# Adapter-IO4-Grove.net
KiCad netlist of a schematic drawn in EAGLE
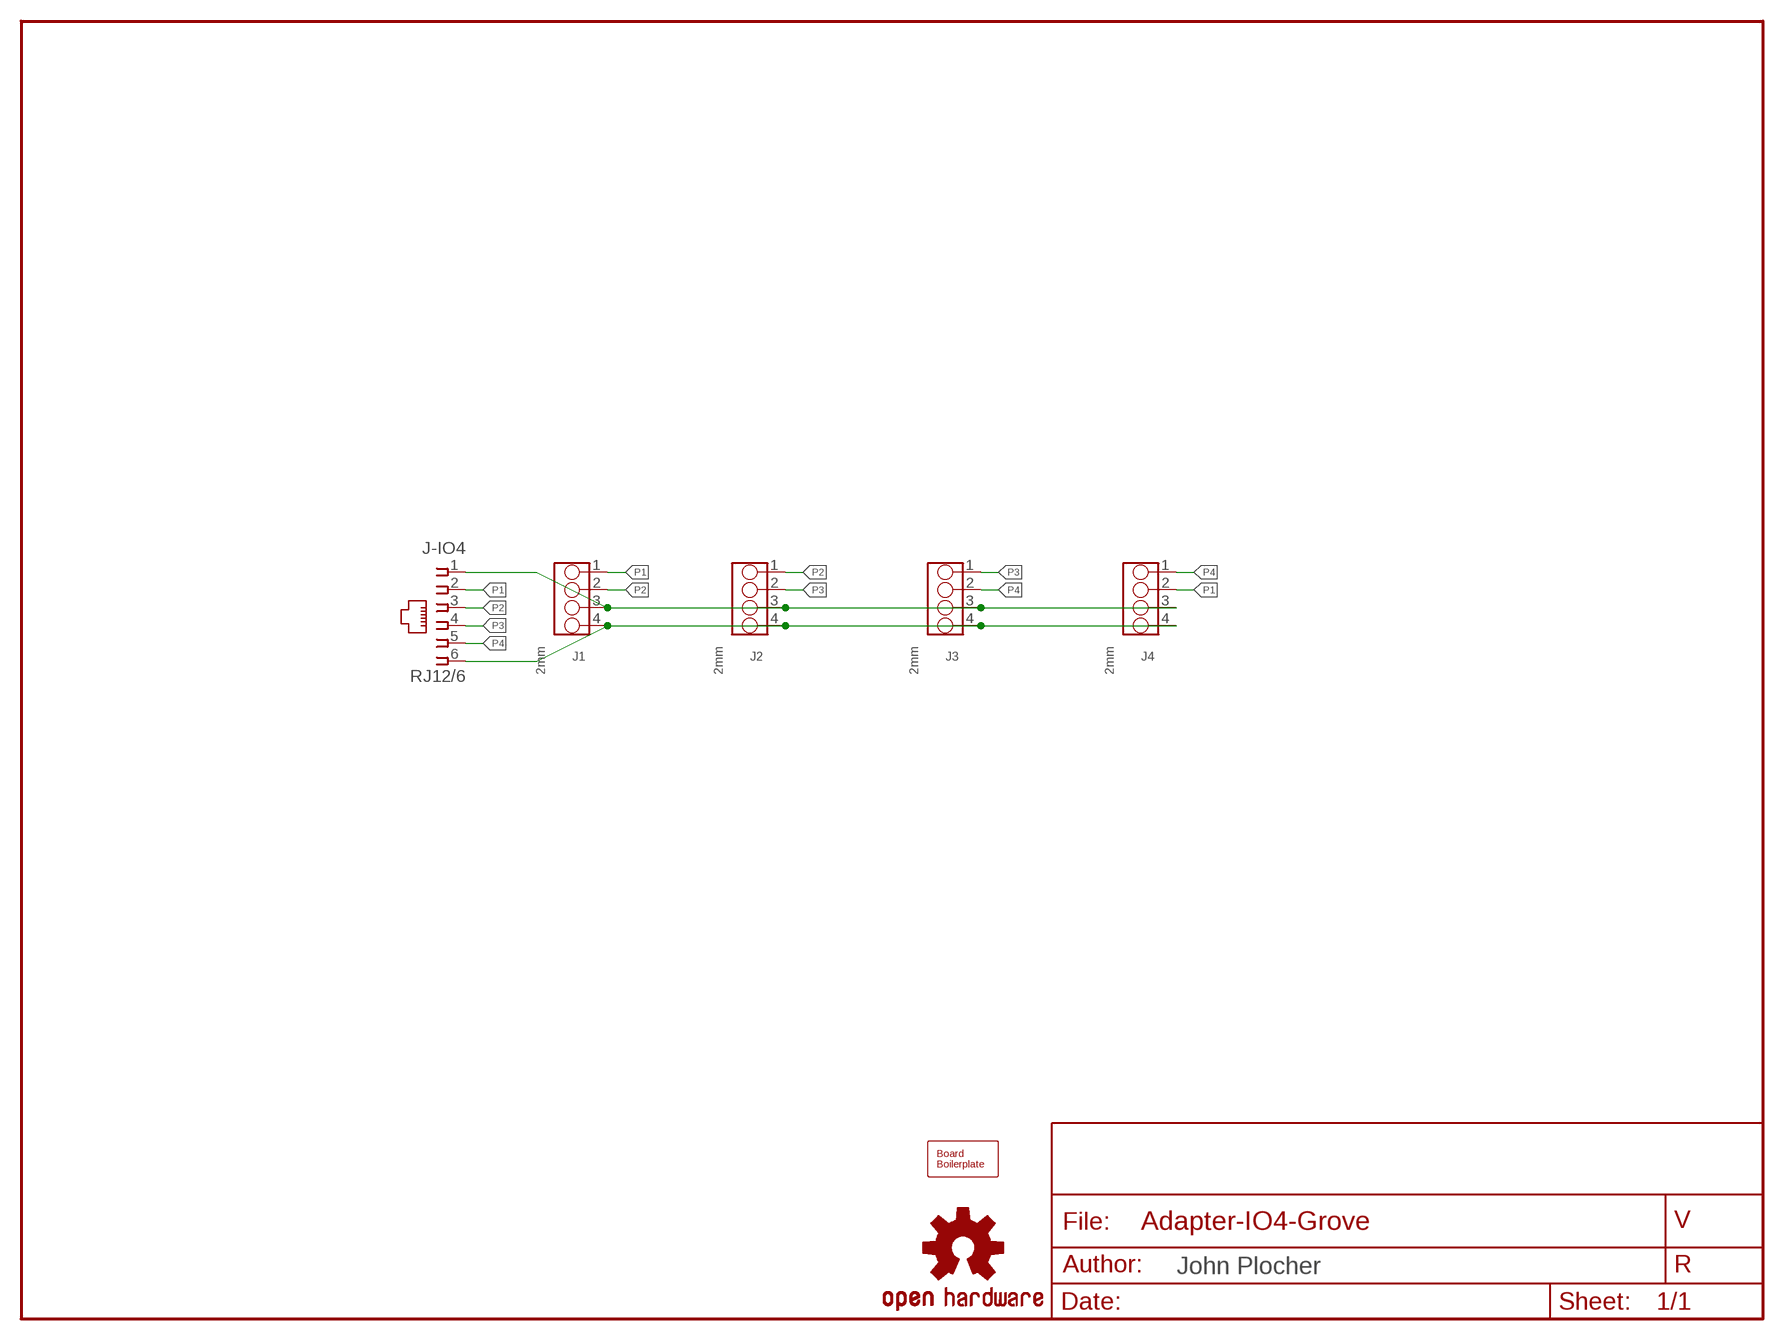
[diagram p0: schematic, sheet 1]

(export (version "E")
  (design (tool "Eeschema 10.0.6"))
  (components
    (comp (ref "J-IO4")
      (value "RJ12/6")
      (footprint "eagle-import:RJ25-INVERTED")
      (libsource (lib "eagle-import") (part "CONNECTOR-RJ25-43860-2-MOLEX"))
    )
    (comp (ref "J1")
      (value "2mm")
      (footprint "eagle-import:4P-2.0")
      (libsource (lib "eagle-import") (part "CONNECTOR-GROVE-4P-2.0-3470130P1"))
    )
    (comp (ref "J2")
      (value "2mm")
      (footprint "eagle-import:4P-2.0")
      (libsource (lib "eagle-import") (part "CONNECTOR-GROVE-4P-2.0-3470130P1"))
    )
    (comp (ref "J3")
      (value "2mm")
      (footprint "eagle-import:4P-2.0")
      (libsource (lib "eagle-import") (part "CONNECTOR-GROVE-4P-2.0-3470130P1"))
    )
    (comp (ref "J4")
      (value "2mm")
      (footprint "eagle-import:4P-2.0")
      (libsource (lib "eagle-import") (part "CONNECTOR-GROVE-4P-2.0-3470130P1"))
    )
    (comp (ref "LOGO1")
      (value "OSHW")
      (footprint "eagle-import:OSHW-LOGO-L")
      (libsource (lib "eagle-import") (part "DOC-OSHW-LOGO-L"))
    )
    (comp (ref "U$1")
      (value "BOARD")
      (footprint "eagle-import:BOARD-SEEED5X5")
      (libsource (lib "eagle-import") (part "BOARD50X50"))
    )
  )
  (nets
    (net (code "1") (name "Net-(J-IO4-Pad1)") (class "Default")
      (node (ref "J-IO4") (pin "1") (pinfunction "1_1") (pintype "passive"))
      (node (ref "J1") (pin "3") (pinfunction "3_3") (pintype "bidirectional"))
      (node (ref "J2") (pin "3") (pinfunction "3_3") (pintype "bidirectional"))
      (node (ref "J3") (pin "3") (pinfunction "3_3") (pintype "bidirectional"))
      (node (ref "J4") (pin "3") (pinfunction "3_3") (pintype "bidirectional"))
    )
    (net (code "2") (name "Net-(J-IO4-Pad6)") (class "Default")
      (node (ref "J-IO4") (pin "6") (pinfunction "6_6") (pintype "passive"))
      (node (ref "J1") (pin "4") (pinfunction "4_4") (pintype "bidirectional"))
      (node (ref "J2") (pin "4") (pinfunction "4_4") (pintype "bidirectional"))
      (node (ref "J3") (pin "4") (pinfunction "4_4") (pintype "bidirectional"))
      (node (ref "J4") (pin "4") (pinfunction "4_4") (pintype "bidirectional"))
    )
    (net (code "3") (name "P1") (class "Default")
      (node (ref "J-IO4") (pin "2") (pinfunction "2_2") (pintype "passive"))
      (node (ref "J1") (pin "1") (pinfunction "1_1") (pintype "bidirectional"))
      (node (ref "J4") (pin "2") (pinfunction "2_2") (pintype "bidirectional"))
    )
    (net (code "4") (name "P2") (class "Default")
      (node (ref "J-IO4") (pin "3") (pinfunction "3_3") (pintype "passive"))
      (node (ref "J1") (pin "2") (pinfunction "2_2") (pintype "bidirectional"))
      (node (ref "J2") (pin "1") (pinfunction "1_1") (pintype "bidirectional"))
    )
    (net (code "5") (name "P3") (class "Default")
      (node (ref "J-IO4") (pin "4") (pinfunction "4_4") (pintype "passive"))
      (node (ref "J2") (pin "2") (pinfunction "2_2") (pintype "bidirectional"))
      (node (ref "J3") (pin "1") (pinfunction "1_1") (pintype "bidirectional"))
    )
    (net (code "6") (name "P4") (class "Default")
      (node (ref "J-IO4") (pin "5") (pinfunction "5_5") (pintype "passive"))
      (node (ref "J3") (pin "2") (pinfunction "2_2") (pintype "bidirectional"))
      (node (ref "J4") (pin "1") (pinfunction "1_1") (pintype "bidirectional"))
    )
  )
)
